# 780-00030_rev1_Pg1_Extended_GPIO_Apps_bo.net
KiCad netlist of a schematic drawn in Altium Designer
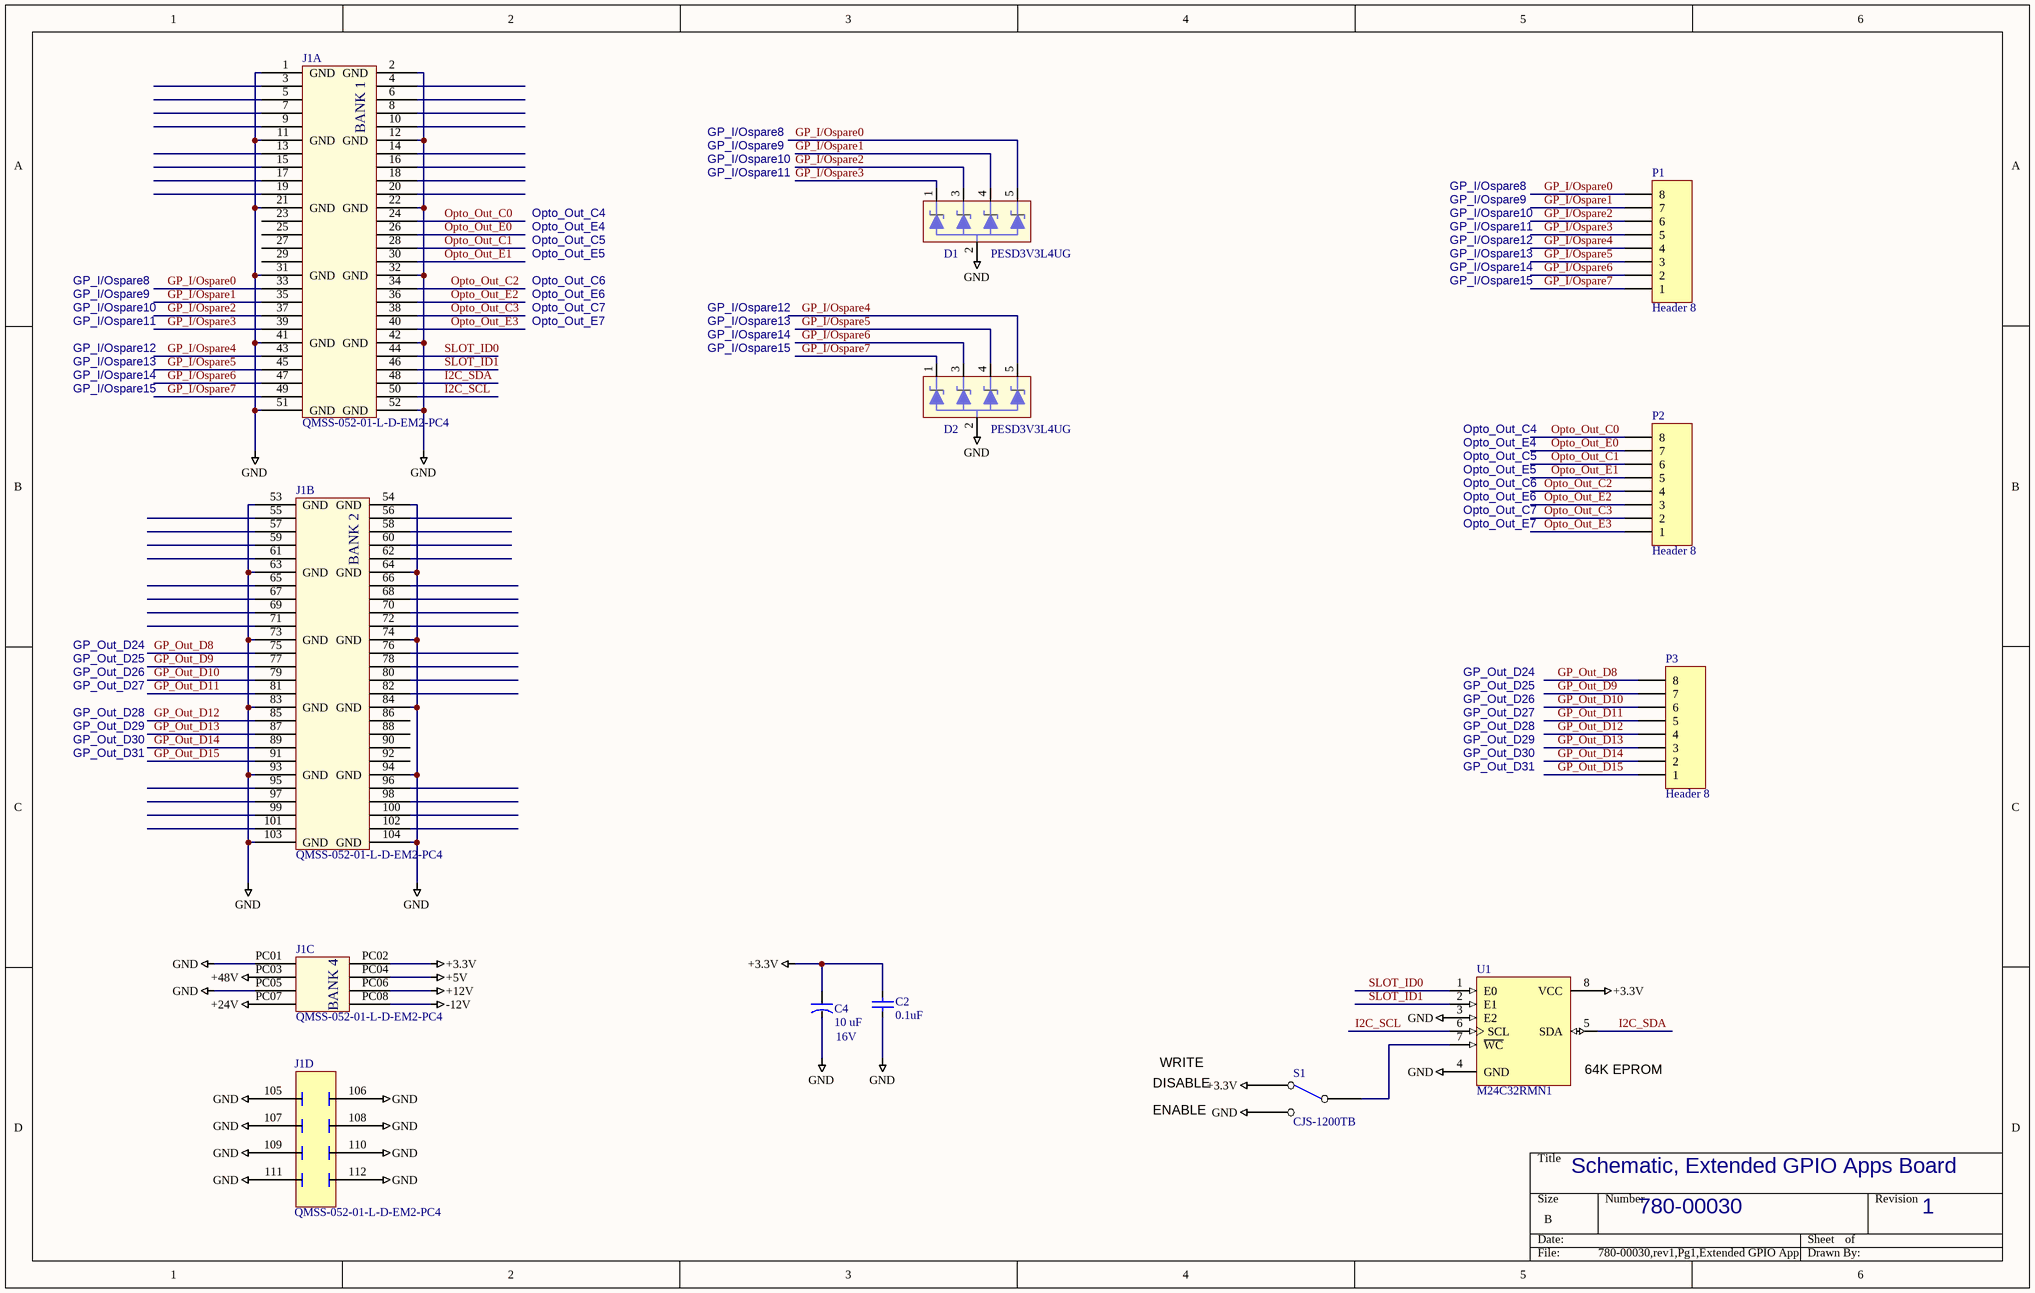
[diagram p0: 780-00030,rev1,Pg1,Extended GPIO Apps board.SchDoc]

(export (version "E")
  (design (tool "Eeschema 10.0.6"))
  (components
    (comp (ref "C2")
      (value "0.1uF")
      (footprint "SMD_0805")
      (description "Capacitor")
      (fields (field (name "Comment") "Cap SMD"))
      (libsource (lib "Richs Schematic Components") (part "Cap SMD"))
    )
    (comp (ref "C4")
      (value "16V")
      (footprint "SMD_CAP_3216")
      (description "outline 3.2mm x 1.6mm")
      (fields (field (name "MANUFACTURER") "KEMET") (field (name "ALTIUM_VALUE") "10 uF"))
      (libsource (lib "Richs Schematic Components") (part "Cap Tant 16V"))
    )
    (comp (ref "D1")
      (value "PESD3V3L4UG")
      (footprint "SOT-353")
      (description "Quad ESD Diode 3.3V")
      (fields (field (name "MANUFACTURER") "NXP"))
      (libsource (lib "Richs Schematic Components") (part "ESD Diode 3.3V Quad"))
    )
    (comp (ref "D2")
      (value "PESD3V3L4UG")
      (footprint "SOT-353")
      (description "Quad ESD Diode 3.3V")
      (fields (field (name "MANUFACTURER") "NXP"))
      (libsource (lib "Richs Schematic Components") (part "ESD Diode 3.3V Quad"))
    )
    (comp (ref "J1")
      (value "QMSS-052-01-L-D-EM2-PC4")
      (footprint "QMS EDGE PWR PINS - 104 pin")
      (description "SAMTEC QMSS EDGE W/PWR PINS")
      (fields (field (name "MANUFACTURER") "SAMTEC") (field (name "Comment") "QMSS-EM-PC4-104pin"))
      (libsource (lib "Richs Schematic Components") (part "QMSS-EM-PC4-104pin"))
    )
    (comp (ref "P1")
      (value "Header 8")
      (footprint "HDR1X8 for IDC")
      (description "Header, 8-Pin")
      (libsource (lib "Richs Schematic Components") (part "Header 8"))
    )
    (comp (ref "P2")
      (value "Header 8")
      (footprint "HDR1X8 for IDC")
      (description "Header, 8-Pin")
      (libsource (lib "Richs Schematic Components") (part "Header 8"))
    )
    (comp (ref "P3")
      (value "Header 8")
      (footprint "HDR1X8 for IDC")
      (description "Header, 8-Pin")
      (libsource (lib "Richs Schematic Components") (part "Header 8"))
    )
    (comp (ref "S1")
      (value "CJS-1200TB")
      (footprint "CAS-120A")
      (fields (field (name "MANUFACTURER") "Copal Electronics"))
      (libsource (lib "JON_1_Library") (part "SW_SPDT_DOUG"))
    )
    (comp (ref "U1")
      (value "M24C32RMN1")
      (footprint "SOP8_N")
      (description "32 Kbit Serial I²C Bus EEPROM")
      (fields (field (name "MANUFACTURER") "ST Micro"))
      (libsource (lib "ST Memory EEPROM Serial") (part "M24C32RMN1"))
    )
  )
  (nets
    (net (code "1") (name "+3.3V") (class "Default")
      (node (ref "C2") (pin "1") (pinfunction "1_1") (pintype "passive"))
      (node (ref "C4") (pin "1") (pinfunction "1_1") (pintype "passive"))
      (node (ref "J1") (pin "PC02") (pinfunction "PC02_PC02") (pintype "passive"))
      (node (ref "S1") (pin "3") (pinfunction "NC_3") (pintype "passive"))
      (node (ref "U1") (pin "8") (pinfunction "VCC_8") (pintype "power_in"))
    )
    (net (code "2") (name "+5V") (class "Default")
      (node (ref "J1") (pin "PC04") (pinfunction "PC04_PC04") (pintype "passive"))
    )
    (net (code "3") (name "+12V") (class "Default")
      (node (ref "J1") (pin "PC06") (pinfunction "PC06_PC06") (pintype "passive"))
    )
    (net (code "4") (name "+24V") (class "Default")
      (node (ref "J1") (pin "PC07") (pinfunction "PC07_PC07") (pintype "passive"))
    )
    (net (code "5") (name "+48V") (class "Default")
      (node (ref "J1") (pin "PC03") (pinfunction "PC03_PC03") (pintype "passive"))
    )
    (net (code "6") (name "-12V") (class "Default")
      (node (ref "J1") (pin "PC08") (pinfunction "PC08_PC08") (pintype "passive"))
    )
    (net (code "7") (name "/GP_I{slash}Ospare0") (class "Default")
      (node (ref "D1") (pin "5") (pintype "passive"))
      (node (ref "J1") (pin "33") (pinfunction "33_33") (pintype "passive"))
      (node (ref "P1") (pin "8") (pinfunction "8_8") (pintype "passive"))
    )
    (net (code "8") (name "/GP_I{slash}Ospare1") (class "Default")
      (node (ref "D1") (pin "4") (pintype "passive"))
      (node (ref "J1") (pin "35") (pinfunction "35_35") (pintype "passive"))
      (node (ref "P1") (pin "7") (pinfunction "7_7") (pintype "passive"))
    )
    (net (code "9") (name "/GP_I{slash}Ospare2") (class "Default")
      (node (ref "D1") (pin "3") (pintype "passive"))
      (node (ref "J1") (pin "37") (pinfunction "37_37") (pintype "passive"))
      (node (ref "P1") (pin "6") (pinfunction "6_6") (pintype "passive"))
    )
    (net (code "10") (name "/GP_I{slash}Ospare3") (class "Default")
      (node (ref "D1") (pin "1") (pintype "passive"))
      (node (ref "J1") (pin "39") (pinfunction "39_39") (pintype "passive"))
      (node (ref "P1") (pin "5") (pinfunction "5_5") (pintype "passive"))
    )
    (net (code "11") (name "/GP_I{slash}Ospare4") (class "Default")
      (node (ref "D2") (pin "5") (pintype "passive"))
      (node (ref "J1") (pin "43") (pinfunction "43_43") (pintype "passive"))
      (node (ref "P1") (pin "4") (pinfunction "4_4") (pintype "passive"))
    )
    (net (code "12") (name "/GP_I{slash}Ospare5") (class "Default")
      (node (ref "D2") (pin "4") (pintype "passive"))
      (node (ref "J1") (pin "45") (pinfunction "45_45") (pintype "passive"))
      (node (ref "P1") (pin "3") (pinfunction "3_3") (pintype "passive"))
    )
    (net (code "13") (name "/GP_I{slash}Ospare6") (class "Default")
      (node (ref "D2") (pin "3") (pintype "passive"))
      (node (ref "J1") (pin "47") (pinfunction "47_47") (pintype "passive"))
      (node (ref "P1") (pin "2") (pinfunction "2_2") (pintype "passive"))
    )
    (net (code "14") (name "/GP_I{slash}Ospare7") (class "Default")
      (node (ref "D2") (pin "1") (pintype "passive"))
      (node (ref "J1") (pin "49") (pinfunction "49_49") (pintype "passive"))
      (node (ref "P1") (pin "1") (pinfunction "1_1") (pintype "passive"))
    )
    (net (code "15") (name "/GP_Out_D8") (class "Default")
      (node (ref "J1") (pin "75") (pinfunction "75_75") (pintype "passive"))
      (node (ref "P3") (pin "8") (pinfunction "8_8") (pintype "passive"))
    )
    (net (code "16") (name "/GP_Out_D9") (class "Default")
      (node (ref "J1") (pin "77") (pinfunction "77_77") (pintype "passive"))
      (node (ref "P3") (pin "7") (pinfunction "7_7") (pintype "passive"))
    )
    (net (code "17") (name "/GP_Out_D10") (class "Default")
      (node (ref "J1") (pin "79") (pinfunction "79_79") (pintype "passive"))
      (node (ref "P3") (pin "6") (pinfunction "6_6") (pintype "passive"))
    )
    (net (code "18") (name "/GP_Out_D11") (class "Default")
      (node (ref "J1") (pin "81") (pinfunction "81_81") (pintype "passive"))
      (node (ref "P3") (pin "5") (pinfunction "5_5") (pintype "passive"))
    )
    (net (code "19") (name "/GP_Out_D12") (class "Default")
      (node (ref "J1") (pin "85") (pinfunction "85_85") (pintype "passive"))
      (node (ref "P3") (pin "4") (pinfunction "4_4") (pintype "passive"))
    )
    (net (code "20") (name "/GP_Out_D13") (class "Default")
      (node (ref "J1") (pin "87") (pinfunction "87_87") (pintype "passive"))
      (node (ref "P3") (pin "3") (pinfunction "3_3") (pintype "passive"))
    )
    (net (code "21") (name "/GP_Out_D14") (class "Default")
      (node (ref "J1") (pin "89") (pinfunction "89_89") (pintype "passive"))
      (node (ref "P3") (pin "2") (pinfunction "2_2") (pintype "passive"))
    )
    (net (code "22") (name "/GP_Out_D15") (class "Default")
      (node (ref "J1") (pin "91") (pinfunction "91_91") (pintype "passive"))
      (node (ref "P3") (pin "1") (pinfunction "1_1") (pintype "passive"))
    )
    (net (code "23") (name "/I2C_SCL") (class "Default")
      (node (ref "J1") (pin "50") (pinfunction "50_50") (pintype "passive"))
      (node (ref "U1") (pin "6") (pinfunction "SCL_6") (pintype "input"))
    )
    (net (code "24") (name "/I2C_SDA") (class "Default")
      (node (ref "J1") (pin "48") (pinfunction "48_48") (pintype "passive"))
      (node (ref "U1") (pin "5") (pinfunction "SDA_5") (pintype "bidirectional"))
    )
    (net (code "25") (name "/Opto_Out_C0") (class "Default")
      (node (ref "J1") (pin "24") (pinfunction "24_24") (pintype "passive"))
      (node (ref "P2") (pin "8") (pinfunction "8_8") (pintype "passive"))
    )
    (net (code "26") (name "/Opto_Out_C1") (class "Default")
      (node (ref "J1") (pin "28") (pinfunction "28_28") (pintype "passive"))
      (node (ref "P2") (pin "6") (pinfunction "6_6") (pintype "passive"))
    )
    (net (code "27") (name "/Opto_Out_C2") (class "Default")
      (node (ref "J1") (pin "34") (pinfunction "34_34") (pintype "passive"))
      (node (ref "P2") (pin "4") (pinfunction "4_4") (pintype "passive"))
    )
    (net (code "28") (name "/Opto_Out_C3") (class "Default")
      (node (ref "J1") (pin "38") (pinfunction "38_38") (pintype "passive"))
      (node (ref "P2") (pin "2") (pinfunction "2_2") (pintype "passive"))
    )
    (net (code "29") (name "/Opto_Out_E0") (class "Default")
      (node (ref "J1") (pin "26") (pinfunction "26_26") (pintype "passive"))
      (node (ref "P2") (pin "7") (pinfunction "7_7") (pintype "passive"))
    )
    (net (code "30") (name "/Opto_Out_E1") (class "Default")
      (node (ref "J1") (pin "30") (pinfunction "30_30") (pintype "passive"))
      (node (ref "P2") (pin "5") (pinfunction "5_5") (pintype "passive"))
    )
    (net (code "31") (name "/Opto_Out_E2") (class "Default")
      (node (ref "J1") (pin "36") (pinfunction "36_36") (pintype "passive"))
      (node (ref "P2") (pin "3") (pinfunction "3_3") (pintype "passive"))
    )
    (net (code "32") (name "/Opto_Out_E3") (class "Default")
      (node (ref "J1") (pin "40") (pinfunction "40_40") (pintype "passive"))
      (node (ref "P2") (pin "1") (pinfunction "1_1") (pintype "passive"))
    )
    (net (code "33") (name "/SLOT_ID0") (class "Default")
      (node (ref "J1") (pin "44") (pinfunction "44_44") (pintype "passive"))
      (node (ref "U1") (pin "1") (pinfunction "E0_1") (pintype "input"))
    )
    (net (code "34") (name "/SLOT_ID1") (class "Default")
      (node (ref "J1") (pin "46") (pinfunction "46_46") (pintype "passive"))
      (node (ref "U1") (pin "2") (pinfunction "E1_2") (pintype "input"))
    )
    (net (code "35") (name "GND") (class "Default")
      (node (ref "C2") (pin "2") (pinfunction "2_2") (pintype "passive"))
      (node (ref "C4") (pin "2") (pinfunction "2_2") (pintype "passive"))
      (node (ref "D1") (pin "2") (pintype "passive"))
      (node (ref "D2") (pin "2") (pintype "passive"))
      (node (ref "J1") (pin "1") (pinfunction "GND_1") (pintype "passive"))
      (node (ref "J1") (pin "103") (pinfunction "GND_103") (pintype "passive"))
      (node (ref "J1") (pin "104") (pinfunction "GND_104") (pintype "passive"))
      (node (ref "J1") (pin "105") (pinfunction "GND_105") (pintype "passive"))
      (node (ref "J1") (pin "106") (pinfunction "GND_106") (pintype "passive"))
      (node (ref "J1") (pin "107") (pinfunction "GND_107") (pintype "passive"))
      (node (ref "J1") (pin "108") (pinfunction "GND_108") (pintype "passive"))
      (node (ref "J1") (pin "109") (pinfunction "GND_109") (pintype "passive"))
      (node (ref "J1") (pin "11") (pinfunction "GND_11") (pintype "passive"))
      (node (ref "J1") (pin "110") (pinfunction "GND_110") (pintype "passive"))
      (node (ref "J1") (pin "111") (pinfunction "GND_111") (pintype "passive"))
      (node (ref "J1") (pin "112") (pinfunction "GND_112") (pintype "passive"))
      (node (ref "J1") (pin "12") (pinfunction "GND_12") (pintype "passive"))
      (node (ref "J1") (pin "2") (pinfunction "GND_2") (pintype "passive"))
      (node (ref "J1") (pin "21") (pinfunction "GND_21") (pintype "passive"))
      (node (ref "J1") (pin "22") (pinfunction "GND_22") (pintype "passive"))
      (node (ref "J1") (pin "31") (pinfunction "GND_31") (pintype "passive"))
      (node (ref "J1") (pin "32") (pinfunction "GND_32") (pintype "passive"))
      (node (ref "J1") (pin "41") (pinfunction "GND_41") (pintype "passive"))
      (node (ref "J1") (pin "42") (pinfunction "GND_42") (pintype "passive"))
      (node (ref "J1") (pin "51") (pinfunction "GND_51") (pintype "passive"))
      (node (ref "J1") (pin "52") (pinfunction "GND_52") (pintype "passive"))
      (node (ref "J1") (pin "53") (pinfunction "GND_53") (pintype "passive"))
      (node (ref "J1") (pin "54") (pinfunction "GND_54") (pintype "passive"))
      (node (ref "J1") (pin "63") (pinfunction "GND_63") (pintype "passive"))
      (node (ref "J1") (pin "64") (pinfunction "GND_64") (pintype "passive"))
      (node (ref "J1") (pin "73") (pinfunction "GND_73") (pintype "passive"))
      (node (ref "J1") (pin "74") (pinfunction "GND_74") (pintype "passive"))
      (node (ref "J1") (pin "83") (pinfunction "GND_83") (pintype "passive"))
      (node (ref "J1") (pin "84") (pinfunction "GND_84") (pintype "passive"))
      (node (ref "J1") (pin "93") (pinfunction "GND_93") (pintype "passive"))
      (node (ref "J1") (pin "94") (pinfunction "GND_94") (pintype "passive"))
      (node (ref "J1") (pin "PC01") (pinfunction "PC01_PC01") (pintype "passive"))
      (node (ref "J1") (pin "PC05") (pinfunction "PC05_PC05") (pintype "passive"))
      (node (ref "S1") (pin "1") (pinfunction "NO_1") (pintype "passive"))
      (node (ref "U1") (pin "3") (pinfunction "E2_3") (pintype "input"))
      (node (ref "U1") (pin "4") (pinfunction "GND_4") (pintype "power_in"))
    )
    (net (code "36") (name "Net-(S1-COM)") (class "Default")
      (node (ref "S1") (pin "2") (pinfunction "COM_2") (pintype "passive"))
      (node (ref "U1") (pin "7") (pinfunction "~{WC}_7") (pintype "input"))
    )
    (net (code "37") (name "unconnected-(J1-Pad3)") (class "Default")
      (node (ref "J1") (pin "3") (pinfunction "3_3") (pintype "passive"))
    )
    (net (code "38") (name "unconnected-(J1-Pad4)") (class "Default")
      (node (ref "J1") (pin "4") (pinfunction "4_4") (pintype "passive"))
    )
    (net (code "39") (name "unconnected-(J1-Pad5)") (class "Default")
      (node (ref "J1") (pin "5") (pinfunction "5_5") (pintype "passive"))
    )
    (net (code "40") (name "unconnected-(J1-Pad6)") (class "Default")
      (node (ref "J1") (pin "6") (pinfunction "6_6") (pintype "passive"))
    )
    (net (code "41") (name "unconnected-(J1-Pad7)") (class "Default")
      (node (ref "J1") (pin "7") (pinfunction "7_7") (pintype "passive"))
    )
    (net (code "42") (name "unconnected-(J1-Pad8)") (class "Default")
      (node (ref "J1") (pin "8") (pinfunction "8_8") (pintype "passive"))
    )
    (net (code "43") (name "unconnected-(J1-Pad9)") (class "Default")
      (node (ref "J1") (pin "9") (pinfunction "9_9") (pintype "passive"))
    )
    (net (code "44") (name "unconnected-(J1-Pad10)") (class "Default")
      (node (ref "J1") (pin "10") (pinfunction "10_10") (pintype "passive"))
    )
    (net (code "45") (name "unconnected-(J1-Pad13)") (class "Default")
      (node (ref "J1") (pin "13") (pinfunction "13_13") (pintype "passive"))
    )
    (net (code "46") (name "unconnected-(J1-Pad14)") (class "Default")
      (node (ref "J1") (pin "14") (pinfunction "14_14") (pintype "passive"))
    )
    (net (code "47") (name "unconnected-(J1-Pad15)") (class "Default")
      (node (ref "J1") (pin "15") (pinfunction "15_15") (pintype "passive"))
    )
    (net (code "48") (name "unconnected-(J1-Pad16)") (class "Default")
      (node (ref "J1") (pin "16") (pinfunction "16_16") (pintype "passive"))
    )
    (net (code "49") (name "unconnected-(J1-Pad17)") (class "Default")
      (node (ref "J1") (pin "17") (pinfunction "17_17") (pintype "passive"))
    )
    (net (code "50") (name "unconnected-(J1-Pad18)") (class "Default")
      (node (ref "J1") (pin "18") (pinfunction "18_18") (pintype "passive"))
    )
    (net (code "51") (name "unconnected-(J1-Pad19)") (class "Default")
      (node (ref "J1") (pin "19") (pinfunction "19_19") (pintype "passive"))
    )
    (net (code "52") (name "unconnected-(J1-Pad20)") (class "Default")
      (node (ref "J1") (pin "20") (pinfunction "20_20") (pintype "passive"))
    )
    (net (code "53") (name "unconnected-(J1-Pad23)") (class "Default")
      (node (ref "J1") (pin "23") (pinfunction "23_23") (pintype "passive"))
    )
    (net (code "54") (name "unconnected-(J1-Pad25)") (class "Default")
      (node (ref "J1") (pin "25") (pinfunction "25_25") (pintype "passive"))
    )
    (net (code "55") (name "unconnected-(J1-Pad27)") (class "Default")
      (node (ref "J1") (pin "27") (pinfunction "27_27") (pintype "passive"))
    )
    (net (code "56") (name "unconnected-(J1-Pad29)") (class "Default")
      (node (ref "J1") (pin "29") (pinfunction "29_29") (pintype "passive"))
    )
    (net (code "57") (name "unconnected-(J1-Pad55)") (class "Default")
      (node (ref "J1") (pin "55") (pinfunction "55_55") (pintype "passive"))
    )
    (net (code "58") (name "unconnected-(J1-Pad56)") (class "Default")
      (node (ref "J1") (pin "56") (pinfunction "56_56") (pintype "passive"))
    )
    (net (code "59") (name "unconnected-(J1-Pad57)") (class "Default")
      (node (ref "J1") (pin "57") (pinfunction "57_57") (pintype "passive"))
    )
    (net (code "60") (name "unconnected-(J1-Pad58)") (class "Default")
      (node (ref "J1") (pin "58") (pinfunction "58_58") (pintype "passive"))
    )
    (net (code "61") (name "unconnected-(J1-Pad59)") (class "Default")
      (node (ref "J1") (pin "59") (pinfunction "59_59") (pintype "passive"))
    )
    (net (code "62") (name "unconnected-(J1-Pad60)") (class "Default")
      (node (ref "J1") (pin "60") (pinfunction "60_60") (pintype "passive"))
    )
    (net (code "63") (name "unconnected-(J1-Pad61)") (class "Default")
      (node (ref "J1") (pin "61") (pinfunction "61_61") (pintype "passive"))
    )
    (net (code "64") (name "unconnected-(J1-Pad62)") (class "Default")
      (node (ref "J1") (pin "62") (pinfunction "62_62") (pintype "passive"))
    )
    (net (code "65") (name "unconnected-(J1-Pad65)") (class "Default")
      (node (ref "J1") (pin "65") (pinfunction "65_65") (pintype "passive"))
    )
    (net (code "66") (name "unconnected-(J1-Pad66)") (class "Default")
      (node (ref "J1") (pin "66") (pinfunction "66_66") (pintype "passive"))
    )
    (net (code "67") (name "unconnected-(J1-Pad67)") (class "Default")
      (node (ref "J1") (pin "67") (pinfunction "67_67") (pintype "passive"))
    )
    (net (code "68") (name "unconnected-(J1-Pad68)") (class "Default")
      (node (ref "J1") (pin "68") (pinfunction "68_68") (pintype "passive"))
    )
    (net (code "69") (name "unconnected-(J1-Pad69)") (class "Default")
      (node (ref "J1") (pin "69") (pinfunction "69_69") (pintype "passive"))
    )
    (net (code "70") (name "unconnected-(J1-Pad70)") (class "Default")
      (node (ref "J1") (pin "70") (pinfunction "70_70") (pintype "passive"))
    )
    (net (code "71") (name "unconnected-(J1-Pad71)") (class "Default")
      (node (ref "J1") (pin "71") (pinfunction "71_71") (pintype "passive"))
    )
    (net (code "72") (name "unconnected-(J1-Pad72)") (class "Default")
      (node (ref "J1") (pin "72") (pinfunction "72_72") (pintype "passive"))
    )
    (net (code "73") (name "unconnected-(J1-Pad76)") (class "Default")
      (node (ref "J1") (pin "76") (pinfunction "76_76") (pintype "passive"))
    )
    (net (code "74") (name "unconnected-(J1-Pad78)") (class "Default")
      (node (ref "J1") (pin "78") (pinfunction "78_78") (pintype "passive"))
    )
    (net (code "75") (name "unconnected-(J1-Pad80)") (class "Default")
      (node (ref "J1") (pin "80") (pinfunction "80_80") (pintype "passive"))
    )
    (net (code "76") (name "unconnected-(J1-Pad82)") (class "Default")
      (node (ref "J1") (pin "82") (pinfunction "82_82") (pintype "passive"))
    )
    (net (code "77") (name "unconnected-(J1-Pad86)") (class "Default")
      (node (ref "J1") (pin "86") (pinfunction "86_86") (pintype "passive"))
    )
    (net (code "78") (name "unconnected-(J1-Pad88)") (class "Default")
      (node (ref "J1") (pin "88") (pinfunction "88_88") (pintype "passive"))
    )
    (net (code "79") (name "unconnected-(J1-Pad90)") (class "Default")
      (node (ref "J1") (pin "90") (pinfunction "90_90") (pintype "passive"))
    )
    (net (code "80") (name "unconnected-(J1-Pad92)") (class "Default")
      (node (ref "J1") (pin "92") (pinfunction "92_92") (pintype "passive"))
    )
    (net (code "81") (name "unconnected-(J1-Pad95)") (class "Default")
      (node (ref "J1") (pin "95") (pinfunction "95_95") (pintype "passive"))
    )
    (net (code "82") (name "unconnected-(J1-Pad96)") (class "Default")
      (node (ref "J1") (pin "96") (pinfunction "96_96") (pintype "passive"))
    )
    (net (code "83") (name "unconnected-(J1-Pad97)") (class "Default")
      (node (ref "J1") (pin "97") (pinfunction "97_97") (pintype "passive"))
    )
    (net (code "84") (name "unconnected-(J1-Pad98)") (class "Default")
      (node (ref "J1") (pin "98") (pinfunction "98_98") (pintype "passive"))
    )
    (net (code "85") (name "unconnected-(J1-Pad99)") (class "Default")
      (node (ref "J1") (pin "99") (pinfunction "99_99") (pintype "passive"))
    )
    (net (code "86") (name "unconnected-(J1-Pad100)") (class "Default")
      (node (ref "J1") (pin "100") (pinfunction "100_100") (pintype "passive"))
    )
    (net (code "87") (name "unconnected-(J1-Pad101)") (class "Default")
      (node (ref "J1") (pin "101") (pinfunction "101_101") (pintype "passive"))
    )
    (net (code "88") (name "unconnected-(J1-Pad102)") (class "Default")
      (node (ref "J1") (pin "102") (pinfunction "102_102") (pintype "passive"))
    )
  )
)
